# spi-interface-T1M.net
KiCad netlist of a schematic drawn in EAGLE
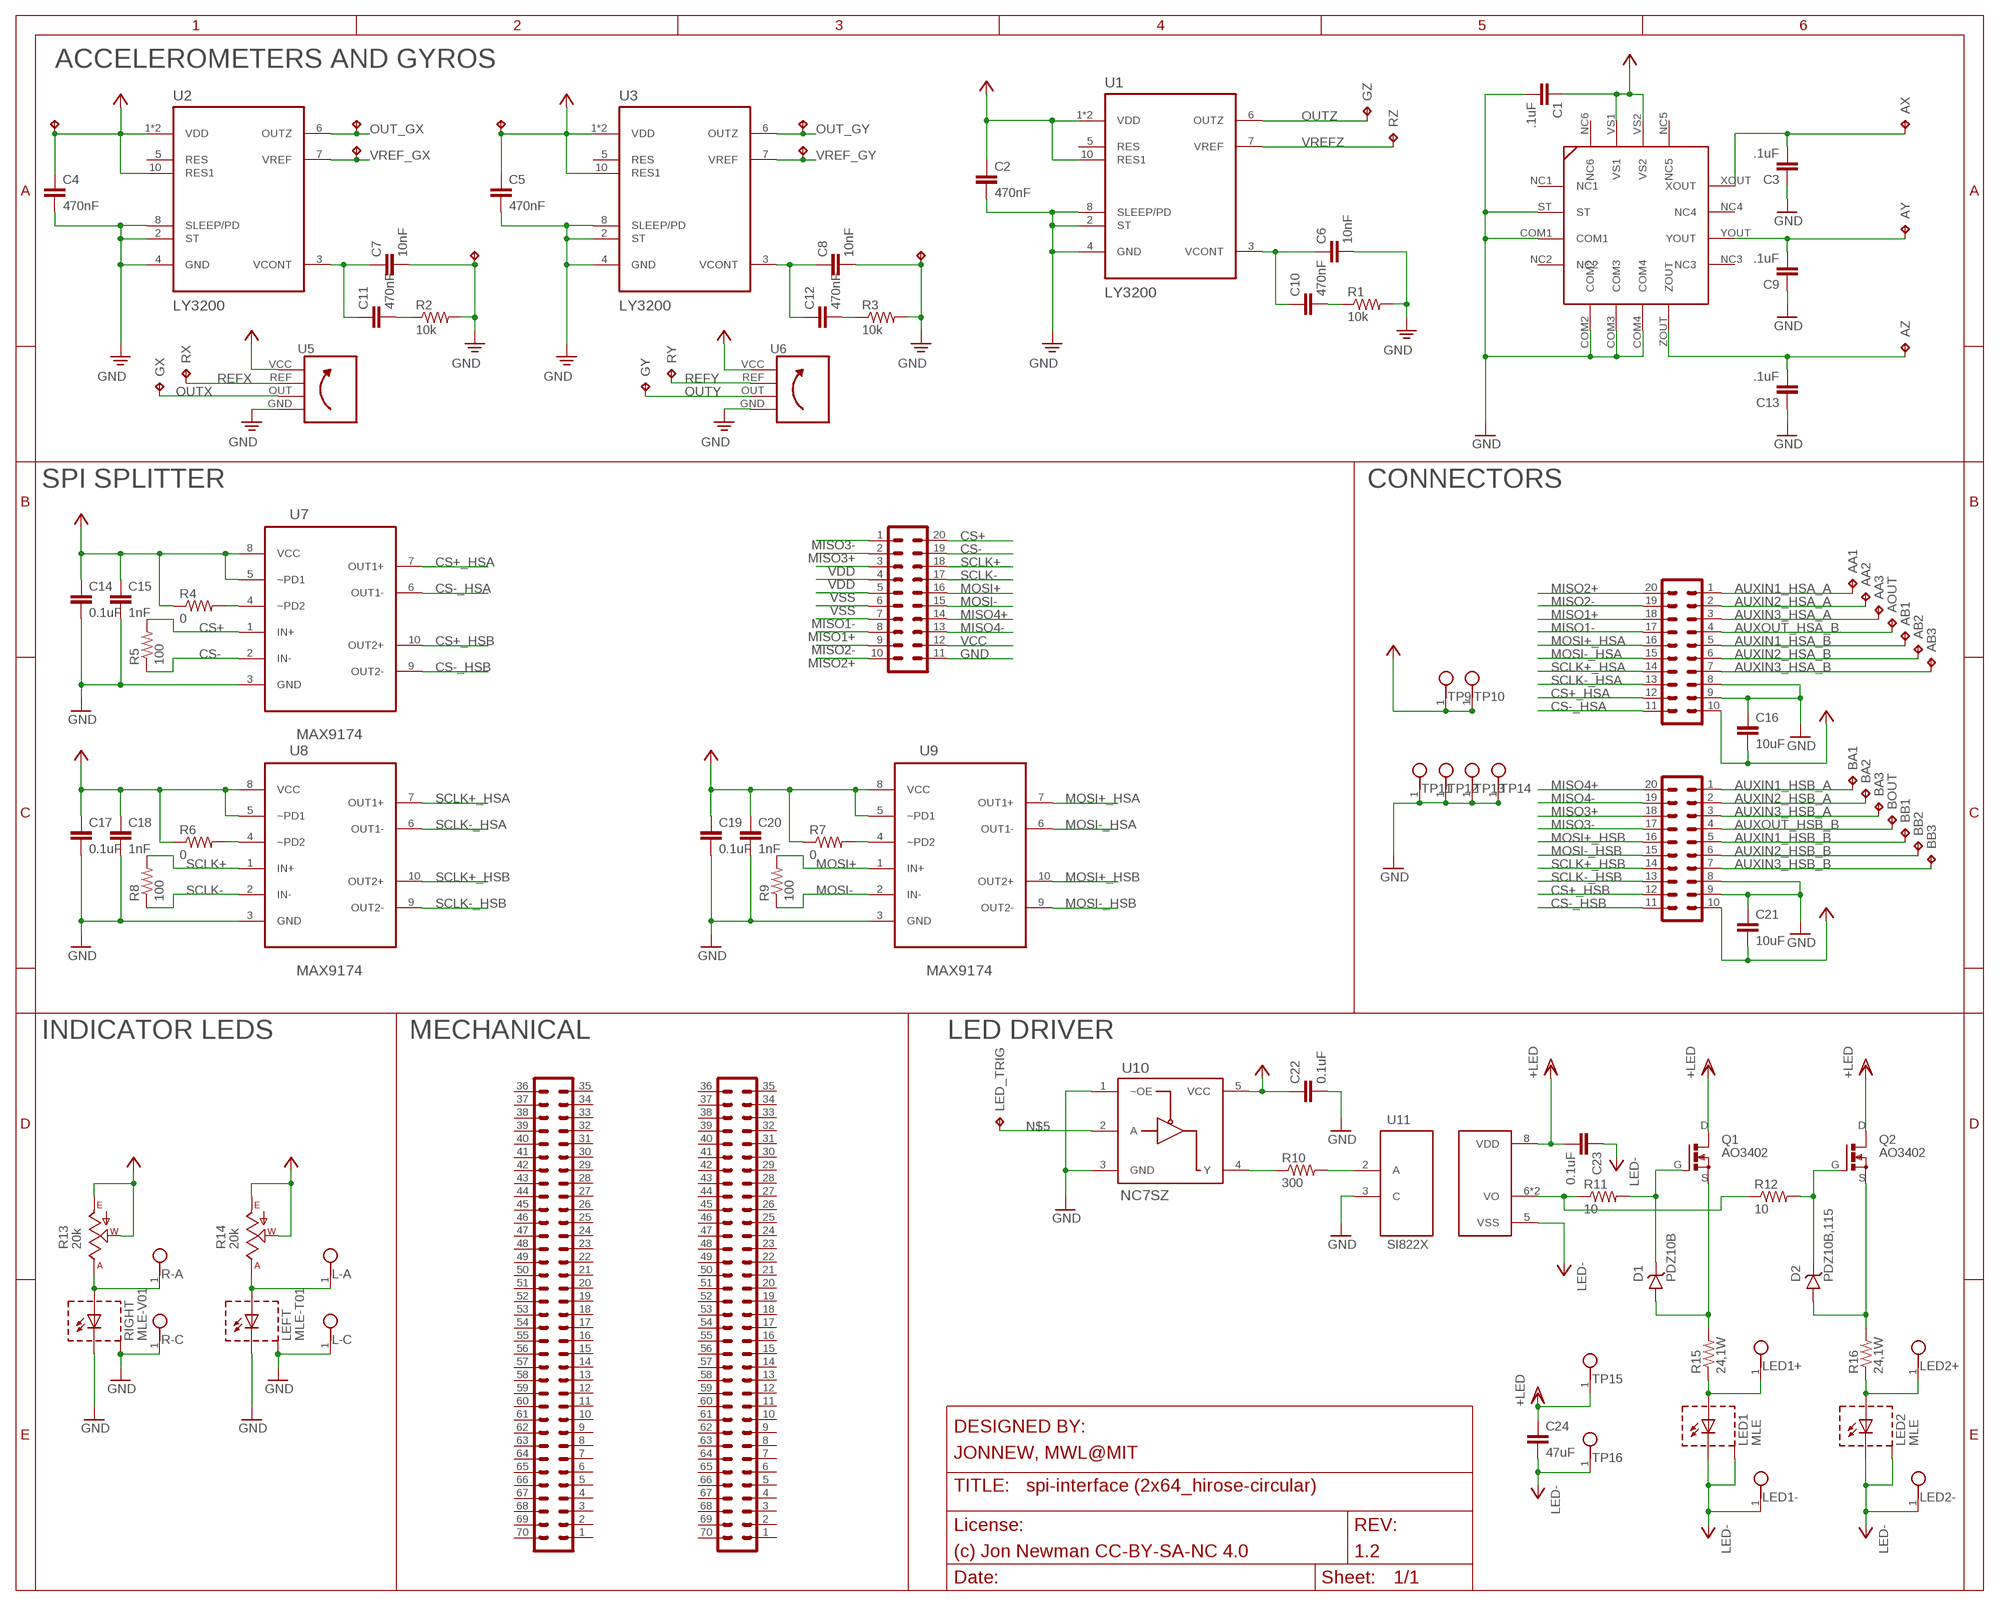
[diagram p0: schematic, sheet 1]

(export (version "E")
  (design (tool "Eeschema 10.0.6"))
  (components
    (comp (ref "AA1")
      (value "TP_0.5MM")
      (footprint "eagle-import:TESTPOINT_0.5MM")
      (libsource (lib "eagle-import") (part "TP_0.5MM"))
    )
    (comp (ref "AA2")
      (value "TP_0.5MM")
      (footprint "eagle-import:TESTPOINT_0.5MM")
      (libsource (lib "eagle-import") (part "TP_0.5MM"))
    )
    (comp (ref "AA3")
      (value "TP_0.5MM")
      (footprint "eagle-import:TESTPOINT_0.5MM")
      (libsource (lib "eagle-import") (part "TP_0.5MM"))
    )
    (comp (ref "AB1")
      (value "TP_0.5MM")
      (footprint "eagle-import:TESTPOINT_0.5MM")
      (libsource (lib "eagle-import") (part "TP_0.5MM"))
    )
    (comp (ref "AB2")
      (value "TP_0.5MM")
      (footprint "eagle-import:TESTPOINT_0.5MM")
      (libsource (lib "eagle-import") (part "TP_0.5MM"))
    )
    (comp (ref "AB3")
      (value "TP_0.5MM")
      (footprint "eagle-import:TESTPOINT_0.5MM")
      (libsource (lib "eagle-import") (part "TP_0.5MM"))
    )
    (comp (ref "AOUT")
      (value "TP_0.5MM")
      (footprint "eagle-import:TESTPOINT_0.5MM")
      (libsource (lib "eagle-import") (part "TP_0.5MM"))
    )
    (comp (ref "AX")
      (value "TP_0.5MM")
      (footprint "eagle-import:TESTPOINT_0.5MM")
      (libsource (lib "eagle-import") (part "TP_0.5MM"))
    )
    (comp (ref "AY")
      (value "TP_0.5MM")
      (footprint "eagle-import:TESTPOINT_0.5MM")
      (libsource (lib "eagle-import") (part "TP_0.5MM"))
    )
    (comp (ref "AZ")
      (value "TP_0.5MM")
      (footprint "eagle-import:TESTPOINT_0.5MM")
      (libsource (lib "eagle-import") (part "TP_0.5MM"))
    )
    (comp (ref "BA1")
      (value "TP_0.5MM")
      (footprint "eagle-import:TESTPOINT_0.5MM")
      (libsource (lib "eagle-import") (part "TP_0.5MM"))
    )
    (comp (ref "BA2")
      (value "TP_0.5MM")
      (footprint "eagle-import:TESTPOINT_0.5MM")
      (libsource (lib "eagle-import") (part "TP_0.5MM"))
    )
    (comp (ref "BA3")
      (value "TP_0.5MM")
      (footprint "eagle-import:TESTPOINT_0.5MM")
      (libsource (lib "eagle-import") (part "TP_0.5MM"))
    )
    (comp (ref "BB1")
      (value "TP_0.5MM")
      (footprint "eagle-import:TESTPOINT_0.5MM")
      (libsource (lib "eagle-import") (part "TP_0.5MM"))
    )
    (comp (ref "BB2")
      (value "TP_0.5MM")
      (footprint "eagle-import:TESTPOINT_0.5MM")
      (libsource (lib "eagle-import") (part "TP_0.5MM"))
    )
    (comp (ref "BB3")
      (value "TP_0.5MM")
      (footprint "eagle-import:TESTPOINT_0.5MM")
      (libsource (lib "eagle-import") (part "TP_0.5MM"))
    )
    (comp (ref "BOUT")
      (value "TP_0.5MM")
      (footprint "eagle-import:TESTPOINT_0.5MM")
      (libsource (lib "eagle-import") (part "TP_0.5MM"))
    )
    (comp (ref "C1")
      (value ".1uF")
      (footprint "eagle-import:0402")
      (libsource (lib "eagle-import") (part "C_0402"))
    )
    (comp (ref "C2")
      (value "470nF")
      (footprint "eagle-import:0201")
      (libsource (lib "eagle-import") (part "jonnew_C_0201"))
    )
    (comp (ref "C3")
      (value ".1uF")
      (footprint "eagle-import:0201")
      (libsource (lib "eagle-import") (part "jonnew_C_0201"))
    )
    (comp (ref "C4")
      (value "470nF")
      (footprint "eagle-import:0201")
      (libsource (lib "eagle-import") (part "jonnew_C_0201"))
    )
    (comp (ref "C5")
      (value "470nF")
      (footprint "eagle-import:0201")
      (libsource (lib "eagle-import") (part "jonnew_C_0201"))
    )
    (comp (ref "C6")
      (value "10nF")
      (footprint "eagle-import:0201")
      (libsource (lib "eagle-import") (part "jonnew_C_0201"))
    )
    (comp (ref "C7")
      (value "10nF")
      (footprint "eagle-import:0201")
      (libsource (lib "eagle-import") (part "jonnew_C_0201"))
    )
    (comp (ref "C8")
      (value "10nF")
      (footprint "eagle-import:0201")
      (libsource (lib "eagle-import") (part "jonnew_C_0201"))
    )
    (comp (ref "C9")
      (value ".1uF")
      (footprint "eagle-import:0201")
      (libsource (lib "eagle-import") (part "jonnew_C_0201"))
    )
    (comp (ref "C10")
      (value "470nF")
      (footprint "eagle-import:0201")
      (libsource (lib "eagle-import") (part "jonnew_C_0201"))
    )
    (comp (ref "C11")
      (value "470nF")
      (footprint "eagle-import:0201")
      (libsource (lib "eagle-import") (part "jonnew_C_0201"))
    )
    (comp (ref "C12")
      (value "470nF")
      (footprint "eagle-import:0201")
      (libsource (lib "eagle-import") (part "jonnew_C_0201"))
    )
    (comp (ref "C13")
      (value ".1uF")
      (footprint "eagle-import:0201")
      (libsource (lib "eagle-import") (part "jonnew_C_0201"))
    )
    (comp (ref "C14")
      (value "0.1uF")
      (footprint "eagle-import:0402")
      (libsource (lib "eagle-import") (part "jonnew_C_0402"))
    )
    (comp (ref "C15")
      (value "1nF")
      (footprint "eagle-import:0201")
      (libsource (lib "eagle-import") (part "jonnew_C_0201"))
    )
    (comp (ref "C16")
      (value "10uF")
      (footprint "eagle-import:0805")
      (fields (field (name "PARTNO") "C2012X5R1Cxxxxxxx"))
      (libsource (lib "eagle-import") (part "C_0805"))
    )
    (comp (ref "C17")
      (value "0.1uF")
      (footprint "eagle-import:0402")
      (libsource (lib "eagle-import") (part "jonnew_C_0402"))
    )
    (comp (ref "C18")
      (value "1nF")
      (footprint "eagle-import:0201")
      (libsource (lib "eagle-import") (part "jonnew_C_0201"))
    )
    (comp (ref "C19")
      (value "0.1uF")
      (footprint "eagle-import:0402")
      (libsource (lib "eagle-import") (part "jonnew_C_0402"))
    )
    (comp (ref "C20")
      (value "1nF")
      (footprint "eagle-import:0201")
      (libsource (lib "eagle-import") (part "jonnew_C_0201"))
    )
    (comp (ref "C21")
      (value "10uF")
      (footprint "eagle-import:0805")
      (fields (field (name "PARTNO") "C2012X5R1Cxxxxxxx"))
      (libsource (lib "eagle-import") (part "C_0805"))
    )
    (comp (ref "C22")
      (value "0.1uF")
      (footprint "eagle-import:0402")
      (libsource (lib "eagle-import") (part "jonnew_C_0402"))
    )
    (comp (ref "C23")
      (value "0.1uF")
      (footprint "eagle-import:0402")
      (libsource (lib "eagle-import") (part "jonnew_C_0402"))
    )
    (comp (ref "C24")
      (value "47uF")
      (footprint "eagle-import:1206")
      (libsource (lib "eagle-import") (part "jonnew_C_1206"))
    )
    (comp (ref "D1")
      (value "PDZ10B")
      (footprint "eagle-import:SOD-323")
      (libsource (lib "eagle-import") (part "Z-DIODE_SOD-323"))
    )
    (comp (ref "D2")
      (value "PDZ10B,115")
      (footprint "eagle-import:SOD-323")
      (libsource (lib "eagle-import") (part "Z-DIODE_SOD-323"))
    )
    (comp (ref "DIO_HSA")
      (value "PINHD-2X10_DF40-20REC")
      (footprint "eagle-import:DF40-20REC")
      (libsource (lib "eagle-import") (part "PINHD-2X10_DF40-20REC"))
    )
    (comp (ref "DIO_HSB")
      (value "PINHD-2X10_DF40-20REC")
      (footprint "eagle-import:DF40-20REC")
      (libsource (lib "eagle-import") (part "PINHD-2X10_DF40-20REC"))
    )
    (comp (ref "GX")
      (value "TP_0.5MM")
      (footprint "eagle-import:TESTPOINT_0.5MM")
      (libsource (lib "eagle-import") (part "TP_0.5MM"))
    )
    (comp (ref "GY")
      (value "TP_0.5MM")
      (footprint "eagle-import:TESTPOINT_0.5MM")
      (libsource (lib "eagle-import") (part "TP_0.5MM"))
    )
    (comp (ref "GZ")
      (value "TP_0.5MM")
      (footprint "eagle-import:TESTPOINT_0.5MM")
      (libsource (lib "eagle-import") (part "TP_0.5MM"))
    )
    (comp (ref "L-A")
      (value "TESTPOINT_SMALL")
      (footprint "eagle-import:TESTPOINT_SMALL")
      (libsource (lib "eagle-import") (part "TESTPOINT_SMALL"))
    )
    (comp (ref "L-C")
      (value "TESTPOINT_SMALL")
      (footprint "eagle-import:TESTPOINT_SMALL")
      (libsource (lib "eagle-import") (part "TESTPOINT_SMALL"))
    )
    (comp (ref "LED1")
      (value "MLE")
      (footprint "eagle-import:LED-MLE")
      (libsource (lib "eagle-import") (part "LED_PKG-BODY"))
    )
    (comp (ref "LED1+")
      (value "TESTPOINT_SMALL")
      (footprint "eagle-import:TESTPOINT_SMALL")
      (libsource (lib "eagle-import") (part "TESTPOINT_SMALL"))
    )
    (comp (ref "LED1-")
      (value "TESTPOINT_SMALL")
      (footprint "eagle-import:TESTPOINT_SMALL")
      (libsource (lib "eagle-import") (part "TESTPOINT_SMALL"))
    )
    (comp (ref "LED2")
      (value "MLE")
      (footprint "eagle-import:LED-MLE")
      (libsource (lib "eagle-import") (part "LED_PKG-BODY"))
    )
    (comp (ref "LED2+")
      (value "TESTPOINT_SMALL")
      (footprint "eagle-import:TESTPOINT_SMALL")
      (libsource (lib "eagle-import") (part "TESTPOINT_SMALL"))
    )
    (comp (ref "LED2-")
      (value "TESTPOINT_SMALL")
      (footprint "eagle-import:TESTPOINT_SMALL")
      (libsource (lib "eagle-import") (part "TESTPOINT_SMALL"))
    )
    (comp (ref "LED_TRIG")
      (value "TP_0.5MM")
      (footprint "eagle-import:TESTPOINT_0.5MM")
      (libsource (lib "eagle-import") (part "TP_0.5MM"))
    )
    (comp (ref "LEFT")
      (value "MLE-T01")
      (footprint "eagle-import:LED-MLE")
      (libsource (lib "eagle-import") (part "LED_PKG-BODY"))
    )
    (comp (ref "MECH_E0B")
      (value "PINHD-2X35_DF40REC")
      (footprint "eagle-import:DF40-70REC")
      (libsource (lib "eagle-import") (part "PINHD-2X35_DF40REC"))
    )
    (comp (ref "MECH_W0B")
      (value "PINHD-2X35_DF40REC")
      (footprint "eagle-import:DF40-70REC")
      (libsource (lib "eagle-import") (part "PINHD-2X35_DF40REC"))
    )
    (comp (ref "Q1")
      (value "AO3402")
      (footprint "eagle-import:SOT23-GSD")
      (libsource (lib "eagle-import") (part "N-MOSFET_SOT23-GSD"))
    )
    (comp (ref "Q2")
      (value "AO3402")
      (footprint "eagle-import:SOT23-GSD")
      (libsource (lib "eagle-import") (part "N-MOSFET_SOT23-GSD"))
    )
    (comp (ref "R-A")
      (value "TESTPOINT_SMALL")
      (footprint "eagle-import:TESTPOINT_SMALL")
      (libsource (lib "eagle-import") (part "TESTPOINT_SMALL"))
    )
    (comp (ref "R-C")
      (value "TESTPOINT_SMALL")
      (footprint "eagle-import:TESTPOINT_SMALL")
      (libsource (lib "eagle-import") (part "TESTPOINT_SMALL"))
    )
    (comp (ref "R1")
      (value "10k")
      (footprint "eagle-import:0201")
      (libsource (lib "eagle-import") (part "R_0201"))
    )
    (comp (ref "R2")
      (value "10k")
      (footprint "eagle-import:0201")
      (libsource (lib "eagle-import") (part "R_0201"))
    )
    (comp (ref "R3")
      (value "10k")
      (footprint "eagle-import:0201")
      (libsource (lib "eagle-import") (part "R_0201"))
    )
    (comp (ref "R4")
      (value "0")
      (footprint "eagle-import:0201")
      (libsource (lib "eagle-import") (part "R_0201"))
    )
    (comp (ref "R5")
      (value "100")
      (footprint "eagle-import:0201")
      (libsource (lib "eagle-import") (part "R_0201"))
    )
    (comp (ref "R6")
      (value "0")
      (footprint "eagle-import:0201")
      (libsource (lib "eagle-import") (part "R_0201"))
    )
    (comp (ref "R7")
      (value "0")
      (footprint "eagle-import:0201")
      (libsource (lib "eagle-import") (part "R_0201"))
    )
    (comp (ref "R8")
      (value "100")
      (footprint "eagle-import:0201")
      (libsource (lib "eagle-import") (part "R_0201"))
    )
    (comp (ref "R9")
      (value "100")
      (footprint "eagle-import:0201")
      (libsource (lib "eagle-import") (part "R_0201"))
    )
    (comp (ref "R10")
      (value "300")
      (footprint "eagle-import:0402")
      (libsource (lib "eagle-import") (part "R_0402"))
    )
    (comp (ref "R11")
      (value "10")
      (footprint "eagle-import:0402")
      (libsource (lib "eagle-import") (part "R_0402"))
    )
    (comp (ref "R12")
      (value "10")
      (footprint "eagle-import:0402")
      (libsource (lib "eagle-import") (part "R_0402"))
    )
    (comp (ref "R13")
      (value "20k")
      (footprint "eagle-import:SM-42_43W")
      (libsource (lib "eagle-import") (part "TRIM_US-SM-42/43W"))
    )
    (comp (ref "R14")
      (value "20k")
      (footprint "eagle-import:SM-42_43W")
      (libsource (lib "eagle-import") (part "TRIM_US-SM-42/43W"))
    )
    (comp (ref "R15")
      (value "24,1W")
      (footprint "eagle-import:0805")
      (libsource (lib "eagle-import") (part "R_0805"))
    )
    (comp (ref "R16")
      (value "24,1W")
      (footprint "eagle-import:0805")
      (libsource (lib "eagle-import") (part "R_0805"))
    )
    (comp (ref "RIGHT")
      (value "MLE-V01")
      (footprint "eagle-import:LED-MLE")
      (libsource (lib "eagle-import") (part "LED_PKG-BODY"))
    )
    (comp (ref "RX")
      (value "TP_0.5MM")
      (footprint "eagle-import:TESTPOINT_0.5MM")
      (libsource (lib "eagle-import") (part "TP_0.5MM"))
    )
    (comp (ref "RY")
      (value "TP_0.5MM")
      (footprint "eagle-import:TESTPOINT_0.5MM")
      (libsource (lib "eagle-import") (part "TP_0.5MM"))
    )
    (comp (ref "RZ")
      (value "TP_0.5MM")
      (footprint "eagle-import:TESTPOINT_0.5MM")
      (libsource (lib "eagle-import") (part "TP_0.5MM"))
    )
    (comp (ref "TETHER")
      (value "T1M-10-T-DV")
      (footprint "eagle-import:T1M-10-T-DV")
      (libsource (lib "eagle-import") (part "PINHD-2X10_T1M"))
    )
    (comp (ref "TP1")
      (value "TPTP08SQ")
      (footprint "eagle-import:TP08SQ")
      (libsource (lib "eagle-import") (part "TPTP08SQ"))
    )
    (comp (ref "TP2")
      (value "TPTP08SQ")
      (footprint "eagle-import:TP08SQ")
      (libsource (lib "eagle-import") (part "TPTP08SQ"))
    )
    (comp (ref "TP3")
      (value "TPTP08SQ")
      (footprint "eagle-import:TP08SQ")
      (libsource (lib "eagle-import") (part "TPTP08SQ"))
    )
    (comp (ref "TP4")
      (value "TPTP08SQ")
      (footprint "eagle-import:TP08SQ")
      (libsource (lib "eagle-import") (part "TPTP08SQ"))
    )
    (comp (ref "TP5")
      (value "TPTP08SQ")
      (footprint "eagle-import:TP08SQ")
      (libsource (lib "eagle-import") (part "TPTP08SQ"))
    )
    (comp (ref "TP6")
      (value "TPTP08SQ")
      (footprint "eagle-import:TP08SQ")
      (libsource (lib "eagle-import") (part "TPTP08SQ"))
    )
    (comp (ref "TP7")
      (value "TPTP08SQ")
      (footprint "eagle-import:TP08SQ")
      (libsource (lib "eagle-import") (part "TPTP08SQ"))
    )
    (comp (ref "TP8")
      (value "TPTP08SQ")
      (footprint "eagle-import:TP08SQ")
      (libsource (lib "eagle-import") (part "TPTP08SQ"))
    )
    (comp (ref "TP9")
      (value "TESTPOINT_SMALL")
      (footprint "eagle-import:TESTPOINT_SMALL")
      (libsource (lib "eagle-import") (part "TESTPOINT_SMALL"))
    )
    (comp (ref "TP10")
      (value "TESTPOINT_SMALL")
      (footprint "eagle-import:TESTPOINT_SMALL")
      (libsource (lib "eagle-import") (part "TESTPOINT_SMALL"))
    )
    (comp (ref "TP11")
      (value "TESTPOINT_SMALL")
      (footprint "eagle-import:TESTPOINT_SMALL")
      (libsource (lib "eagle-import") (part "TESTPOINT_SMALL"))
    )
    (comp (ref "TP12")
      (value "TESTPOINT_SMALL")
      (footprint "eagle-import:TESTPOINT_SMALL")
      (libsource (lib "eagle-import") (part "TESTPOINT_SMALL"))
    )
    (comp (ref "TP13")
      (value "TESTPOINT_SMALL")
      (footprint "eagle-import:TESTPOINT_SMALL")
      (libsource (lib "eagle-import") (part "TESTPOINT_SMALL"))
    )
    (comp (ref "TP14")
      (value "TESTPOINT_SMALL")
      (footprint "eagle-import:TESTPOINT_SMALL")
      (libsource (lib "eagle-import") (part "TESTPOINT_SMALL"))
    )
    (comp (ref "TP15")
      (value "TESTPOINT_SMALL")
      (footprint "eagle-import:TESTPOINT_SMALL")
      (libsource (lib "eagle-import") (part "TESTPOINT_SMALL"))
    )
    (comp (ref "TP16")
      (value "TESTPOINT_SMALL")
      (footprint "eagle-import:TESTPOINT_SMALL")
      (libsource (lib "eagle-import") (part "TESTPOINT_SMALL"))
    )
    (comp (ref "U1")
      (value "LY3200")
      (footprint "eagle-import:LGA-10-COMPACT")
      (libsource (lib "eagle-import") (part "LY3200ALH_LGA-10-COMPACT"))
    )
    (comp (ref "U2")
      (value "LY3200")
      (footprint "eagle-import:LGA-10-COMPACT")
      (libsource (lib "eagle-import") (part "LY3200ALH_LGA-10-COMPACT"))
    )
    (comp (ref "U3")
      (value "LY3200")
      (footprint "eagle-import:LGA-10-COMPACT")
      (libsource (lib "eagle-import") (part "LY3200ALH_LGA-10-COMPACT"))
    )
    (comp (ref "U4")
      (value "ADXL335")
      (footprint "eagle-import:ADXL335")
      (libsource (lib "eagle-import") (part "ADXL335"))
    )
    (comp (ref "U5")
      (value "LY3200-VERT-MODULE")
      (footprint "eagle-import:LY3200-VERT-MODULE")
      (libsource (lib "eagle-import") (part "LY3200-VERT-MODULE"))
    )
    (comp (ref "U6")
      (value "LY3200-VERT-MODULE")
      (footprint "eagle-import:LY3200-VERT-MODULE")
      (libsource (lib "eagle-import") (part "LY3200-VERT-MODULE"))
    )
    (comp (ref "U7")
      (value "MAX9174")
      (footprint "eagle-import:10-UMAX")
      (libsource (lib "eagle-import") (part "MAX9174_UMAX"))
    )
    (comp (ref "U8")
      (value "MAX9174")
      (footprint "eagle-import:10-UMAX")
      (libsource (lib "eagle-import") (part "MAX9174_UMAX"))
    )
    (comp (ref "U9")
      (value "MAX9174")
      (footprint "eagle-import:10-UMAX")
      (libsource (lib "eagle-import") (part "MAX9174_UMAX"))
    )
    (comp (ref "U10")
      (value "NC7SZ")
      (footprint "eagle-import:SOT-23-5")
      (libsource (lib "eagle-import") (part "NC7SZ125"))
    )
    (comp (ref "U11")
      (value "SI822X")
      (footprint "eagle-import:SOIC127P500X400-8N")
      (libsource (lib "eagle-import") (part "SI822X"))
    )
  )
  (nets
    (net (code "1") (name "+LED") (class "Default")
      (node (ref "C23") (pin "2") (pinfunction "2_2") (pintype "passive"))
      (node (ref "C24") (pin "1") (pinfunction "1_1") (pintype "passive"))
      (node (ref "Q1") (pin "D") (pinfunction "D_D") (pintype "bidirectional"))
      (node (ref "Q2") (pin "D") (pinfunction "D_D") (pintype "bidirectional"))
      (node (ref "TETHER") (pin "3") (pinfunction "3_3") (pintype "bidirectional"))
      (node (ref "TETHER") (pin "4") (pinfunction "4_4") (pintype "bidirectional"))
      (node (ref "TP15") (pin "1") (pinfunction "1_1") (pintype "passive"))
      (node (ref "U11") (pin "8") (pinfunction "VDD_8") (pintype "power_in"))
    )
    (net (code "2") (name "/AUXIN1_HSA_A") (class "Default")
      (node (ref "AA1") (pin "1") (pinfunction "TP_1") (pintype "input"))
      (node (ref "DIO_HSA") (pin "1") (pinfunction "1_1") (pintype "bidirectional"))
    )
    (net (code "3") (name "/AUXIN1_HSA_B") (class "Default")
      (node (ref "AB1") (pin "1") (pinfunction "TP_1") (pintype "input"))
      (node (ref "DIO_HSA") (pin "5") (pinfunction "5_5") (pintype "bidirectional"))
    )
    (net (code "4") (name "/AUXIN1_HSB_A") (class "Default")
      (node (ref "BA1") (pin "1") (pinfunction "TP_1") (pintype "input"))
      (node (ref "DIO_HSB") (pin "1") (pinfunction "1_1") (pintype "bidirectional"))
    )
    (net (code "5") (name "/AUXIN1_HSB_B") (class "Default")
      (node (ref "BB1") (pin "1") (pinfunction "TP_1") (pintype "input"))
      (node (ref "DIO_HSB") (pin "5") (pinfunction "5_5") (pintype "bidirectional"))
    )
    (net (code "6") (name "/AUXIN2_HSA_A") (class "Default")
      (node (ref "AA2") (pin "1") (pinfunction "TP_1") (pintype "input"))
      (node (ref "DIO_HSA") (pin "2") (pinfunction "2_2") (pintype "bidirectional"))
    )
    (net (code "7") (name "/AUXIN2_HSA_B") (class "Default")
      (node (ref "AB2") (pin "1") (pinfunction "TP_1") (pintype "input"))
      (node (ref "DIO_HSA") (pin "6") (pinfunction "6_6") (pintype "bidirectional"))
    )
    (net (code "8") (name "/AUXIN2_HSB_A") (class "Default")
      (node (ref "BA2") (pin "1") (pinfunction "TP_1") (pintype "input"))
      (node (ref "DIO_HSB") (pin "2") (pinfunction "2_2") (pintype "bidirectional"))
    )
    (net (code "9") (name "/AUXIN2_HSB_B") (class "Default")
      (node (ref "BB2") (pin "1") (pinfunction "TP_1") (pintype "input"))
      (node (ref "DIO_HSB") (pin "6") (pinfunction "6_6") (pintype "bidirectional"))
    )
    (net (code "10") (name "/AUXIN3_HSA_A") (class "Default")
      (node (ref "AA3") (pin "1") (pinfunction "TP_1") (pintype "input"))
      (node (ref "DIO_HSA") (pin "3") (pinfunction "3_3") (pintype "bidirectional"))
    )
    (net (code "11") (name "/AUXIN3_HSA_B") (class "Default")
      (node (ref "AB3") (pin "1") (pinfunction "TP_1") (pintype "input"))
      (node (ref "DIO_HSA") (pin "7") (pinfunction "7_7") (pintype "bidirectional"))
    )
    (net (code "12") (name "/AUXIN3_HSB_A") (class "Default")
      (node (ref "BA3") (pin "1") (pinfunction "TP_1") (pintype "input"))
      (node (ref "DIO_HSB") (pin "3") (pinfunction "3_3") (pintype "bidirectional"))
    )
    (net (code "13") (name "/AUXIN3_HSB_B") (class "Default")
      (node (ref "BB3") (pin "1") (pinfunction "TP_1") (pintype "input"))
      (node (ref "DIO_HSB") (pin "7") (pinfunction "7_7") (pintype "bidirectional"))
    )
    (net (code "14") (name "/AUXOUT_HSA_B") (class "Default")
      (node (ref "AOUT") (pin "1") (pinfunction "TP_1") (pintype "input"))
      (node (ref "DIO_HSA") (pin "4") (pinfunction "4_4") (pintype "bidirectional"))
    )
    (net (code "15") (name "/AUXOUT_HSB_B") (class "Default")
      (node (ref "BOUT") (pin "1") (pinfunction "TP_1") (pintype "input"))
      (node (ref "DIO_HSB") (pin "4") (pinfunction "4_4") (pintype "bidirectional"))
    )
    (net (code "16") (name "/CS+") (class "Default")
      (node (ref "R5") (pin "2") (pinfunction "2_2") (pintype "passive"))
      (node (ref "TETHER") (pin "20") (pinfunction "20_20") (pintype "bidirectional"))
      (node (ref "U7") (pin "1") (pinfunction "IN+_1") (pintype "input"))
    )
    (net (code "17") (name "/CS+_HSA") (class "Default")
      (node (ref "DIO_HSA") (pin "12") (pinfunction "12_12") (pintype "bidirectional"))
      (node (ref "U7") (pin "7") (pinfunction "OUT1+_7") (pintype "output"))
    )
    (net (code "18") (name "/CS+_HSB") (class "Default")
      (node (ref "DIO_HSB") (pin "12") (pinfunction "12_12") (pintype "bidirectional"))
      (node (ref "U7") (pin "10") (pinfunction "OUT2+_10") (pintype "output"))
    )
    (net (code "19") (name "/CS-") (class "Default")
      (node (ref "R5") (pin "1") (pinfunction "1_1") (pintype "passive"))
      (node (ref "TETHER") (pin "19") (pinfunction "19_19") (pintype "bidirectional"))
      (node (ref "U7") (pin "2") (pinfunction "IN-_2") (pintype "input"))
    )
    (net (code "20") (name "/CS-_HSA") (class "Default")
      (node (ref "DIO_HSA") (pin "11") (pinfunction "11_11") (pintype "bidirectional"))
      (node (ref "U7") (pin "6") (pinfunction "OUT1-_6") (pintype "output"))
    )
    (net (code "21") (name "/CS-_HSB") (class "Default")
      (node (ref "DIO_HSB") (pin "11") (pinfunction "11_11") (pintype "bidirectional"))
      (node (ref "U7") (pin "9") (pinfunction "OUT2-_9") (pintype "output"))
    )
    (net (code "22") (name "/MISO1+") (class "Default")
      (node (ref "DIO_HSA") (pin "18") (pinfunction "18_18") (pintype "bidirectional"))
      (node (ref "TETHER") (pin "8") (pinfunction "8_8") (pintype "bidirectional"))
    )
    (net (code "23") (name "/MISO1-") (class "Default")
      (node (ref "DIO_HSA") (pin "17") (pinfunction "17_17") (pintype "bidirectional"))
      (node (ref "TETHER") (pin "7") (pinfunction "7_7") (pintype "bidirectional"))
    )
    (net (code "24") (name "/MISO2+") (class "Default")
      (node (ref "DIO_HSA") (pin "20") (pinfunction "20_20") (pintype "bidirectional"))
      (node (ref "TETHER") (pin "10") (pinfunction "10_10") (pintype "bidirectional"))
    )
    (net (code "25") (name "/MISO2-") (class "Default")
      (node (ref "DIO_HSA") (pin "19") (pinfunction "19_19") (pintype "bidirectional"))
      (node (ref "TETHER") (pin "9") (pinfunction "9_9") (pintype "bidirectional"))
    )
    (net (code "26") (name "/MISO3+") (class "Default")
      (node (ref "DIO_HSB") (pin "18") (pinfunction "18_18") (pintype "bidirectional"))
      (node (ref "TETHER") (pin "2") (pinfunction "2_2") (pintype "bidirectional"))
    )
    (net (code "27") (name "/MISO3-") (class "Default")
      (node (ref "DIO_HSB") (pin "17") (pinfunction "17_17") (pintype "bidirectional"))
      (node (ref "TETHER") (pin "1") (pinfunction "1_1") (pintype "bidirectional"))
    )
    (net (code "28") (name "/MISO4+") (class "Default")
      (node (ref "DIO_HSB") (pin "20") (pinfunction "20_20") (pintype "bidirectional"))
      (node (ref "TETHER") (pin "14") (pinfunction "14_14") (pintype "bidirectional"))
    )
    (net (code "29") (name "/MISO4-") (class "Default")
      (node (ref "DIO_HSB") (pin "19") (pinfunction "19_19") (pintype "bidirectional"))
      (node (ref "TETHER") (pin "13") (pinfunction "13_13") (pintype "bidirectional"))
    )
    (net (code "30") (name "/MOSI+") (class "Default")
      (node (ref "R9") (pin "2") (pinfunction "2_2") (pintype "passive"))
      (node (ref "TETHER") (pin "16") (pinfunction "16_16") (pintype "bidirectional"))
      (node (ref "U9") (pin "1") (pinfunction "IN+_1") (pintype "input"))
    )
    (net (code "31") (name "/MOSI+_HSA") (class "Default")
      (node (ref "DIO_HSA") (pin "16") (pinfunction "16_16") (pintype "bidirectional"))
      (node (ref "U9") (pin "7") (pinfunction "OUT1+_7") (pintype "output"))
    )
    (net (code "32") (name "/MOSI+_HSB") (class "Default")
      (node (ref "DIO_HSB") (pin "16") (pinfunction "16_16") (pintype "bidirectional"))
      (node (ref "U9") (pin "10") (pinfunction "OUT2+_10") (pintype "output"))
    )
    (net (code "33") (name "/MOSI-") (class "Default")
      (node (ref "R9") (pin "1") (pinfunction "1_1") (pintype "passive"))
      (node (ref "TETHER") (pin "15") (pinfunction "15_15") (pintype "bidirectional"))
      (node (ref "U9") (pin "2") (pinfunction "IN-_2") (pintype "input"))
    )
    (net (code "34") (name "/MOSI-_HSA") (class "Default")
      (node (ref "DIO_HSA") (pin "15") (pinfunction "15_15") (pintype "bidirectional"))
      (node (ref "U9") (pin "6") (pinfunction "OUT1-_6") (pintype "output"))
    )
    (net (code "35") (name "/MOSI-_HSB") (class "Default")
      (node (ref "DIO_HSB") (pin "15") (pinfunction "15_15") (pintype "bidirectional"))
      (node (ref "U9") (pin "9") (pinfunction "OUT2-_9") (pintype "output"))
    )
    (net (code "36") (name "/N$5") (class "Default")
      (node (ref "LED_TRIG") (pin "1") (pinfunction "TP_1") (pintype "input"))
      (node (ref "U10") (pin "2") (pinfunction "A_2") (pintype "input"))
    )
    (net (code "37") (name "/OUTX") (class "Default")
      (node (ref "GX") (pin "1") (pinfunction "TP_1") (pintype "input"))
      (node (ref "U5") (pin "OUT") (pinfunction "OUT_OUT") (pintype "output"))
    )
    (net (code "38") (name "/OUTY") (class "Default")
      (node (ref "GY") (pin "1") (pinfunction "TP_1") (pintype "input"))
      (node (ref "U6") (pin "OUT") (pinfunction "OUT_OUT") (pintype "output"))
    )
    (net (code "39") (name "/OUTZ") (class "Default")
      (node (ref "GZ") (pin "1") (pinfunction "TP_1") (pintype "input"))
      (node (ref "U1") (pin "6") (pinfunction "OUTZ_6") (pintype "output"))
    )
    (net (code "40") (name "/OUT_GX") (class "Default")
      (node (ref "TP2") (pin "TP") (pinfunction "TP_TP") (pintype "input"))
      (node (ref "U2") (pin "6") (pinfunction "OUTZ_6") (pintype "output"))
    )
    (net (code "41") (name "/OUT_GY") (class "Default")
      (node (ref "TP4") (pin "TP") (pinfunction "TP_TP") (pintype "input"))
      (node (ref "U3") (pin "6") (pinfunction "OUTZ_6") (pintype "output"))
    )
    (net (code "42") (name "/REFX") (class "Default")
      (node (ref "RX") (pin "1") (pinfunction "TP_1") (pintype "input"))
      (node (ref "U5") (pin "REF") (pinfunction "REF_REF") (pintype "output"))
    )
    (net (code "43") (name "/REFY") (class "Default")
      (node (ref "RY") (pin "1") (pinfunction "TP_1") (pintype "input"))
      (node (ref "U6") (pin "REF") (pinfunction "REF_REF") (pintype "output"))
    )
    (net (code "44") (name "/SCLK+") (class "Default")
      (node (ref "R8") (pin "2") (pinfunction "2_2") (pintype "passive"))
      (node (ref "TETHER") (pin "18") (pinfunction "18_18") (pintype "bidirectional"))
      (node (ref "U8") (pin "1") (pinfunction "IN+_1") (pintype "input"))
    )
    (net (code "45") (name "/SCLK+_HSA") (class "Default")
      (node (ref "DIO_HSA") (pin "14") (pinfunction "14_14") (pintype "bidirectional"))
      (node (ref "U8") (pin "7") (pinfunction "OUT1+_7") (pintype "output"))
    )
    (net (code "46") (name "/SCLK+_HSB") (class "Default")
      (node (ref "DIO_HSB") (pin "14") (pinfunction "14_14") (pintype "bidirectional"))
      (node (ref "U8") (pin "10") (pinfunction "OUT2+_10") (pintype "output"))
    )
    (net (code "47") (name "/SCLK-") (class "Default")
      (node (ref "R8") (pin "1") (pinfunction "1_1") (pintype "passive"))
      (node (ref "TETHER") (pin "17") (pinfunction "17_17") (pintype "bidirectional"))
      (node (ref "U8") (pin "2") (pinfunction "IN-_2") (pintype "input"))
    )
    (net (code "48") (name "/SCLK-_HSA") (class "Default")
      (node (ref "DIO_HSA") (pin "13") (pinfunction "13_13") (pintype "bidirectional"))
      (node (ref "U8") (pin "6") (pinfunction "OUT1-_6") (pintype "output"))
    )
    (net (code "49") (name "/SCLK-_HSB") (class "Default")
      (node (ref "DIO_HSB") (pin "13") (pinfunction "13_13") (pintype "bidirectional"))
      (node (ref "U8") (pin "9") (pinfunction "OUT2-_9") (pintype "output"))
    )
    (net (code "50") (name "/VREFZ") (class "Default")
      (node (ref "RZ") (pin "1") (pinfunction "TP_1") (pintype "input"))
      (node (ref "U1") (pin "7") (pinfunction "VREF_7") (pintype "output"))
    )
    (net (code "51") (name "/VREF_GX") (class "Default")
      (node (ref "TP5") (pin "TP") (pinfunction "TP_TP") (pintype "input"))
      (node (ref "U2") (pin "7") (pinfunction "VREF_7") (pintype "output"))
    )
    (net (code "52") (name "/VREF_GY") (class "Default")
      (node (ref "TP6") (pin "TP") (pinfunction "TP_TP") (pintype "input"))
      (node (ref "U3") (pin "7") (pinfunction "VREF_7") (pintype "output"))
    )
    (net (code "53") (name "GND") (class "Default")
      (node (ref "C1") (pin "2") (pinfunction "2_2") (pintype "passive"))
      (node (ref "C13") (pin "1") (pinfunction "1_1") (pintype "passive"))
      (node (ref "C14") (pin "2") (pinfunction "2_2") (pintype "passive"))
      (node (ref "C15") (pin "2") (pinfunction "2_2") (pintype "passive"))
      (node (ref "C16") (pin "1") (pinfunction "1_1") (pintype "passive"))
      (node (ref "C17") (pin "2") (pinfunction "2_2") (pintype "passive"))
      (node (ref "C18") (pin "2") (pinfunction "2_2") (pintype "passive"))
      (node (ref "C19") (pin "2") (pinfunction "2_2") (pintype "passive"))
      (node (ref "C2") (pin "2") (pinfunction "2_2") (pintype "passive"))
      (node (ref "C20") (pin "2") (pinfunction "2_2") (pintype "passive"))
      (node (ref "C21") (pin "1") (pinfunction "1_1") (pintype "passive"))
      (node (ref "C22") (pin "2") (pinfunction "2_2") (pintype "passive"))
      (node (ref "C3") (pin "1") (pinfunction "1_1") (pintype "passive"))
      (node (ref "C4") (pin "2") (pinfunction "2_2") (pintype "passive"))
      (node (ref "C5") (pin "2") (pinfunction "2_2") (pintype "passive"))
      (node (ref "C6") (pin "2") (pinfunction "2_2") (pintype "passive"))
      (node (ref "C7") (pin "2") (pinfunction "2_2") (pintype "passive"))
      (node (ref "C8") (pin "2") (pinfunction "2_2") (pintype "passive"))
      (node (ref "C9") (pin "1") (pinfunction "1_1") (pintype "passive"))
      (node (ref "DIO_HSA") (pin "8") (pinfunction "8_8") (pintype "bidirectional"))
      (node (ref "DIO_HSA") (pin "9") (pinfunction "9_9") (pintype "bidirectional"))
      (node (ref "DIO_HSB") (pin "8") (pinfunction "8_8") (pintype "bidirectional"))
      (node (ref "DIO_HSB") (pin "9") (pinfunction "9_9") (pintype "bidirectional"))
      (node (ref "L-C") (pin "1") (pinfunction "1_1") (pintype "passive"))
      (node (ref "LEFT") (pin "C1") (pinfunction "C_C1") (pintype "passive"))
      (node (ref "LEFT") (pin "C2") (pinfunction "C_C2") (pintype "passive"))
      (node (ref "LEFT") (pin "HS") (pinfunction "BODY_HS") (pintype "passive"))
      (node (ref "R-C") (pin "1") (pinfunction "1_1") (pintype "passive"))
      (node (ref "R1") (pin "2") (pinfunction "2_2") (pintype "passive"))
      (node (ref "R2") (pin "2") (pinfunction "2_2") (pintype "passive"))
      (node (ref "R3") (pin "2") (pinfunction "2_2") (pintype "passive"))
      (node (ref "RIGHT") (pin "C1") (pinfunction "C_C1") (pintype "passive"))
      (node (ref "RIGHT") (pin "C2") (pinfunction "C_C2") (pintype "passive"))
      (node (ref "RIGHT") (pin "HS") (pinfunction "BODY_HS") (pintype "passive"))
      (node (ref "TETHER") (pin "11") (pinfunction "11_11") (pintype "bidirectional"))
      (node (ref "TP11") (pin "1") (pinfunction "1_1") (pintype "passive"))
      (node (ref "TP12") (pin "1") (pinfunction "1_1") (pintype "passive"))
      (node (ref "TP13") (pin "1") (pinfunction "1_1") (pintype "passive"))
      (node (ref "TP14") (pin "1") (pinfunction "1_1") (pintype "passive"))
      (node (ref "TP7") (pin "TP") (pinfunction "TP_TP") (pintype "input"))
      (node (ref "TP8") (pin "TP") (pinfunction "TP_TP") (pintype "input"))
      (node (ref "U1") (pin "2") (pinfunction "ST_2") (pintype "bidirectional"))
      (node (ref "U1") (pin "4") (pinfunction "GND_4") (pintype "power_in"))
      (node (ref "U1") (pin "8") (pinfunction "SLEEP/PD_8") (pintype "bidirectional"))
      (node (ref "U10") (pin "1") (pinfunction "~{OE}_1") (pintype "input"))
      (node (ref "U10") (pin "3") (pinfunction "GND_3") (pintype "power_in"))
      (node (ref "U11") (pin "3") (pinfunction "C_3") (pintype "bidirectional"))
      (node (ref "U2") (pin "2") (pinfunction "ST_2") (pintype "bidirectional"))
      (node (ref "U2") (pin "4") (pinfunction "GND_4") (pintype "power_in"))
      (node (ref "U2") (pin "8") (pinfunction "SLEEP/PD_8") (pintype "bidirectional"))
      (node (ref "U3") (pin "2") (pinfunction "ST_2") (pintype "bidirectional"))
      (node (ref "U3") (pin "4") (pinfunction "GND_4") (pintype "power_in"))
      (node (ref "U3") (pin "8") (pinfunction "SLEEP/PD_8") (pintype "bidirectional"))
      (node (ref "U4") (pin "COM1") (pinfunction "COM1_COM1") (pintype "bidirectional"))
      (node (ref "U4") (pin "COM2") (pinfunction "COM2_COM2") (pintype "bidirectional"))
      (node (ref "U4") (pin "COM3") (pinfunction "COM3_COM3") (pintype "bidirectional"))
      (node (ref "U4") (pin "COM4") (pinfunction "COM4_COM4") (pintype "bidirectional"))
      (node (ref "U4") (pin "ST") (pinfunction "ST_ST") (pintype "bidirectional"))
      (node (ref "U5") (pin "GND") (pinfunction "GND_GND") (pintype "power_in"))
      (node (ref "U6") (pin "GND") (pinfunction "GND_GND") (pintype "power_in"))
      (node (ref "U7") (pin "3") (pinfunction "GND_3") (pintype "power_in"))
      (node (ref "U8") (pin "3") (pinfunction "GND_3") (pintype "power_in"))
      (node (ref "U9") (pin "3") (pinfunction "GND_3") (pintype "power_in"))
    )
    (net (code "54") (name "LED-") (class "Default")
      (node (ref "C23") (pin "1") (pinfunction "1_1") (pintype "passive"))
      (node (ref "C24") (pin "2") (pinfunction "2_2") (pintype "passive"))
      (node (ref "LED1") (pin "C1") (pinfunction "C_C1") (pintype "passive"))
      (node (ref "LED1") (pin "C2") (pinfunction "C_C2") (pintype "passive"))
      (node (ref "LED1") (pin "HS") (pinfunction "BODY_HS") (pintype "passive"))
      (node (ref "LED1-") (pin "1") (pinfunction "1_1") (pintype "passive"))
      (node (ref "LED2") (pin "C1") (pinfunction "C_C1") (pintype "passive"))
      (node (ref "LED2") (pin "C2") (pinfunction "C_C2") (pintype "passive"))
      (node (ref "LED2") (pin "HS") (pinfunction "BODY_HS") (pintype "passive"))
      (node (ref "LED2-") (pin "1") (pinfunction "1_1") (pintype "passive"))
      (node (ref "TETHER") (pin "5") (pinfunction "5_5") (pintype "bidirectional"))
      (node (ref "TETHER") (pin "6") (pinfunction "6_6") (pintype "bidirectional"))
      (node (ref "TP16") (pin "1") (pinfunction "1_1") (pintype "passive"))
      (node (ref "U11") (pin "5") (pinfunction "VSS_5") (pintype "power_in"))
    )
    (net (code "55") (name "Net-(AX-TP)") (class "Default")
      (node (ref "AX") (pin "1") (pinfunction "TP_1") (pintype "input"))
      (node (ref "C3") (pin "2") (pinfunction "2_2") (pintype "passive"))
      (node (ref "U4") (pin "XOUT") (pinfunction "XOUT_XOUT") (pintype "bidirectional"))
    )
    (net (code "56") (name "Net-(AY-TP)") (class "Default")
      (node (ref "AY") (pin "1") (pinfunction "TP_1") (pintype "input"))
      (node (ref "C9") (pin "2") (pinfunction "2_2") (pintype "passive"))
      (node (ref "U4") (pin "YOUT") (pinfunction "YOUT_YOUT") (pintype "bidirectional"))
    )
    (net (code "57") (name "Net-(AZ-TP)") (class "Default")
      (node (ref "AZ") (pin "1") (pinfunction "TP_1") (pintype "input"))
      (node (ref "C13") (pin "2") (pinfunction "2_2") (pintype "passive"))
      (node (ref "U4") (pin "ZOUT") (pinfunction "ZOUT_ZOUT") (pintype "bidirectional"))
    )
    (net (code "58") (name "Net-(C10-Pad2)") (class "Default")
      (node (ref "C10") (pin "2") (pinfunction "2_2") (pintype "passive"))
      (node (ref "R1") (pin "1") (pinfunction "1_1") (pintype "passive"))
    )
    (net (code "59") (name "Net-(C11-Pad2)") (class "Default")
      (node (ref "C11") (pin "2") (pinfunction "2_2") (pintype "passive"))
      (node (ref "R2") (pin "1") (pinfunction "1_1") (pintype "passive"))
    )
    (net (code "60") (name "Net-(C12-Pad2)") (class "Default")
      (node (ref "C12") (pin "2") (pinfunction "2_2") (pintype "passive"))
      (node (ref "R3") (pin "1") (pinfunction "1_1") (pintype "passive"))
    )
    (net (code "61") (name "Net-(D1-PadA)") (class "Default")
      (node (ref "D1") (pin "A") (pinfunction "A_A") (pintype "passive"))
      (node (ref "Q1") (pin "S") (pinfunction "S_S") (pintype "bidirectional"))
      (node (ref "R15") (pin "2") (pinfunction "2_2") (pintype "passive"))
    )
    (net (code "62") (name "Net-(D1-PadC)") (class "Default")
      (node (ref "D1") (pin "C") (pinfunction "C_C") (pintype "passive"))
      (node (ref "Q1") (pin "G") (pinfunction "G_G") (pintype "bidirectional"))
      (node (ref "R11") (pin "2") (pinfunction "2_2") (pintype "passive"))
    )
    (net (code "63") (name "Net-(D2-PadA)") (class "Default")
      (node (ref "D2") (pin "A") (pinfunction "A_A") (pintype "passive"))
      (node (ref "Q2") (pin "S") (pinfunction "S_S") (pintype "bidirectional"))
      (node (ref "R16") (pin "2") (pinfunction "2_2") (pintype "passive"))
    )
    (net (code "64") (name "Net-(D2-PadC)") (class "Default")
      (node (ref "D2") (pin "C") (pinfunction "C_C") (pintype "passive"))
      (node (ref "Q2") (pin "G") (pinfunction "G_G") (pintype "bidirectional"))
      (node (ref "R12") (pin "2") (pinfunction "2_2") (pintype "passive"))
    )
    (net (code "65") (name "Net-(LED1+-Pad1)") (class "Default")
      (node (ref "LED1") (pin "A1") (pinfunction "A_A1") (pintype "passive"))
      (node (ref "LED1") (pin "A2") (pinfunction "A_A2") (pintype "passive"))
      (node (ref "LED1+") (pin "1") (pinfunction "1_1") (pintype "passive"))
      (node (ref "R15") (pin "1") (pinfunction "1_1") (pintype "passive"))
    )
    (net (code "66") (name "Net-(LED2+-Pad1)") (class "Default")
      (node (ref "LED2") (pin "A1") (pinfunction "A_A1") (pintype "passive"))
      (node (ref "LED2") (pin "A2") (pinfunction "A_A2") (pintype "passive"))
      (node (ref "LED2+") (pin "1") (pinfunction "1_1") (pintype "passive"))
      (node (ref "R16") (pin "1") (pinfunction "1_1") (pintype "passive"))
    )
    (net (code "67") (name "Net-(R11-Pad1)") (class "Default")
      (node (ref "R11") (pin "1") (pinfunction "1_1") (pintype "passive"))
      (node (ref "R12") (pin "1") (pinfunction "1_1") (pintype "passive"))
      (node (ref "U11") (pin "6") (pinfunction "VO_6") (pintype "bidirectional"))
      (node (ref "U11") (pin "7") (pinfunction "VO_7") (pintype "bidirectional"))
    )
    (net (code "68") (name "Net-(R13-A)") (class "Default")
      (node (ref "R-A") (pin "1") (pinfunction "1_1") (pintype "passive"))
      (node (ref "R13") (pin "1") (pinfunction "A_1") (pintype "passive"))
      (node (ref "RIGHT") (pin "A1") (pinfunction "A_A1") (pintype "passive"))
      (node (ref "RIGHT") (pin "A2") (pinfunction "A_A2") (pintype "passive"))
    )
    (net (code "69") (name "Net-(R14-A)") (class "Default")
      (node (ref "L-A") (pin "1") (pinfunction "1_1") (pintype "passive"))
      (node (ref "LEFT") (pin "A1") (pinfunction "A_A1") (pintype "passive"))
      (node (ref "LEFT") (pin "A2") (pinfunction "A_A2") (pintype "passive"))
      (node (ref "R14") (pin "1") (pinfunction "A_1") (pintype "passive"))
    )
    (net (code "70") (name "Net-(U1-VCONT)") (class "Default")
      (node (ref "C10") (pin "1") (pinfunction "1_1") (pintype "passive"))
      (node (ref "C6") (pin "1") (pinfunction "1_1") (pintype "passive"))
      (node (ref "U1") (pin "3") (pinfunction "VCONT_3") (pintype "passive"))
    )
    (net (code "71") (name "Net-(U2-VCONT)") (class "Default")
      (node (ref "C11") (pin "1") (pinfunction "1_1") (pintype "passive"))
      (node (ref "C7") (pin "1") (pinfunction "1_1") (pintype "passive"))
      (node (ref "U2") (pin "3") (pinfunction "VCONT_3") (pintype "passive"))
    )
    (net (code "72") (name "Net-(U3-VCONT)") (class "Default")
      (node (ref "C12") (pin "1") (pinfunction "1_1") (pintype "passive"))
      (node (ref "C8") (pin "1") (pinfunction "1_1") (pintype "passive"))
      (node (ref "U3") (pin "3") (pinfunction "VCONT_3") (pintype "passive"))
    )
    (net (code "73") (name "Net-(U7-~{PD2})") (class "Default")
      (node (ref "R4") (pin "2") (pinfunction "2_2") (pintype "passive"))
      (node (ref "U7") (pin "4") (pinfunction "~{PD2}_4") (pintype "passive"))
    )
    (net (code "74") (name "Net-(U8-~{PD2})") (class "Default")
      (node (ref "R6") (pin "2") (pinfunction "2_2") (pintype "passive"))
      (node (ref "U8") (pin "4") (pinfunction "~{PD2}_4") (pintype "passive"))
    )
    (net (code "75") (name "Net-(U9-~{PD2})") (class "Default")
      (node (ref "R7") (pin "2") (pinfunction "2_2") (pintype "passive"))
      (node (ref "U9") (pin "4") (pinfunction "~{PD2}_4") (pintype "passive"))
    )
    (net (code "76") (name "Net-(U10-Y)") (class "Default")
      (node (ref "R10") (pin "1") (pinfunction "1_1") (pintype "passive"))
      (node (ref "U10") (pin "4") (pinfunction "Y_4") (pintype "output"))
    )
    (net (code "77") (name "Net-(U11-A)") (class "Default")
      (node (ref "R10") (pin "2") (pinfunction "2_2") (pintype "passive"))
      (node (ref "U11") (pin "2") (pinfunction "A_2") (pintype "bidirectional"))
    )
    (net (code "78") (name "VCC") (class "Default")
      (node (ref "C1") (pin "1") (pinfunction "1_1") (pintype "passive"))
      (node (ref "C14") (pin "1") (pinfunction "1_1") (pintype "passive"))
      (node (ref "C15") (pin "1") (pinfunction "1_1") (pintype "passive"))
      (node (ref "C16") (pin "2") (pinfunction "2_2") (pintype "passive"))
      (node (ref "C17") (pin "1") (pinfunction "1_1") (pintype "passive"))
      (node (ref "C18") (pin "1") (pinfunction "1_1") (pintype "passive"))
      (node (ref "C19") (pin "1") (pinfunction "1_1") (pintype "passive"))
      (node (ref "C2") (pin "1") (pinfunction "1_1") (pintype "passive"))
      (node (ref "C20") (pin "1") (pinfunction "1_1") (pintype "passive"))
      (node (ref "C21") (pin "2") (pinfunction "2_2") (pintype "passive"))
      (node (ref "C22") (pin "1") (pinfunction "1_1") (pintype "passive"))
      (node (ref "C4") (pin "1") (pinfunction "1_1") (pintype "passive"))
      (node (ref "C5") (pin "1") (pinfunction "1_1") (pintype "passive"))
      (node (ref "DIO_HSA") (pin "10") (pinfunction "10_10") (pintype "bidirectional"))
      (node (ref "DIO_HSB") (pin "10") (pinfunction "10_10") (pintype "bidirectional"))
      (node (ref "R13") (pin "2") (pinfunction "W_2") (pintype "passive"))
      (node (ref "R13") (pin "3") (pinfunction "E_3") (pintype "passive"))
      (node (ref "R14") (pin "2") (pinfunction "W_2") (pintype "passive"))
      (node (ref "R14") (pin "3") (pinfunction "E_3") (pintype "passive"))
      (node (ref "R4") (pin "1") (pinfunction "1_1") (pintype "passive"))
      (node (ref "R6") (pin "1") (pinfunction "1_1") (pintype "passive"))
      (node (ref "R7") (pin "1") (pinfunction "1_1") (pintype "passive"))
      (node (ref "TETHER") (pin "12") (pinfunction "12_12") (pintype "bidirectional"))
      (node (ref "TP1") (pin "TP") (pinfunction "TP_TP") (pintype "input"))
      (node (ref "TP10") (pin "1") (pinfunction "1_1") (pintype "passive"))
      (node (ref "TP3") (pin "TP") (pinfunction "TP_TP") (pintype "input"))
      (node (ref "TP9") (pin "1") (pinfunction "1_1") (pintype "passive"))
      (node (ref "U1") (pin "1") (pinfunction "VDD_1") (pintype "power_in"))
      (node (ref "U1") (pin "10") (pinfunction "RES1_10") (pintype "passive"))
      (node (ref "U1") (pin "9") (pinfunction "VDD_9") (pintype "power_in"))
      (node (ref "U10") (pin "5") (pinfunction "VCC_5") (pintype "power_in"))
      (node (ref "U2") (pin "1") (pinfunction "VDD_1") (pintype "power_in"))
      (node (ref "U2") (pin "10") (pinfunction "RES1_10") (pintype "passive"))
      (node (ref "U2") (pin "9") (pinfunction "VDD_9") (pintype "power_in"))
      (node (ref "U3") (pin "1") (pinfunction "VDD_1") (pintype "power_in"))
      (node (ref "U3") (pin "10") (pinfunction "RES1_10") (pintype "passive"))
      (node (ref "U3") (pin "9") (pinfunction "VDD_9") (pintype "power_in"))
      (node (ref "U4") (pin "VS1") (pinfunction "VS1_VS1") (pintype "bidirectional"))
      (node (ref "U4") (pin "VS2") (pinfunction "VS2_VS2") (pintype "bidirectional"))
      (node (ref "U5") (pin "VCC") (pinfunction "VCC_VCC") (pintype "power_in"))
      (node (ref "U6") (pin "VCC") (pinfunction "VCC_VCC") (pintype "power_in"))
      (node (ref "U7") (pin "5") (pinfunction "~{PD1}_5") (pintype "passive"))
      (node (ref "U7") (pin "8") (pinfunction "VCC_8") (pintype "power_in"))
      (node (ref "U8") (pin "5") (pinfunction "~{PD1}_5") (pintype "passive"))
      (node (ref "U8") (pin "8") (pinfunction "VCC_8") (pintype "power_in"))
      (node (ref "U9") (pin "5") (pinfunction "~{PD1}_5") (pintype "passive"))
      (node (ref "U9") (pin "8") (pinfunction "VCC_8") (pintype "power_in"))
    )
    (net (code "79") (name "unconnected-(MECH_E0B-Pad1)") (class "Default")
      (node (ref "MECH_E0B") (pin "1") (pinfunction "1_1") (pintype "bidirectional"))
    )
    (net (code "80") (name "unconnected-(MECH_E0B-Pad2)") (class "Default")
      (node (ref "MECH_E0B") (pin "2") (pinfunction "2_2") (pintype "bidirectional"))
    )
    (net (code "81") (name "unconnected-(MECH_E0B-Pad3)") (class "Default")
      (node (ref "MECH_E0B") (pin "3") (pinfunction "3_3") (pintype "bidirectional"))
    )
    (net (code "82") (name "unconnected-(MECH_E0B-Pad4)") (class "Default")
      (node (ref "MECH_E0B") (pin "4") (pinfunction "4_4") (pintype "bidirectional"))
    )
    (net (code "83") (name "unconnected-(MECH_E0B-Pad5)") (class "Default")
      (node (ref "MECH_E0B") (pin "5") (pinfunction "5_5") (pintype "bidirectional"))
    )
    (net (code "84") (name "unconnected-(MECH_E0B-Pad6)") (class "Default")
      (node (ref "MECH_E0B") (pin "6") (pinfunction "6_6") (pintype "bidirectional"))
    )
    (net (code "85") (name "unconnected-(MECH_E0B-Pad7)") (class "Default")
      (node (ref "MECH_E0B") (pin "7") (pinfunction "7_7") (pintype "bidirectional"))
    )
    (net (code "86") (name "unconnected-(MECH_E0B-Pad8)") (class "Default")
      (node (ref "MECH_E0B") (pin "8") (pinfunction "8_8") (pintype "bidirectional"))
    )
    (net (code "87") (name "unconnected-(MECH_E0B-Pad9)") (class "Default")
      (node (ref "MECH_E0B") (pin "9") (pinfunction "9_9") (pintype "bidirectional"))
    )
    (net (code "88") (name "unconnected-(MECH_E0B-Pad10)") (class "Default")
      (node (ref "MECH_E0B") (pin "10") (pinfunction "10_10") (pintype "bidirectional"))
    )
    (net (code "89") (name "unconnected-(MECH_E0B-Pad11)") (class "Default")
      (node (ref "MECH_E0B") (pin "11") (pinfunction "11_11") (pintype "bidirectional"))
    )
    (net (code "90") (name "unconnected-(MECH_E0B-Pad12)") (class "Default")
      (node (ref "MECH_E0B") (pin "12") (pinfunction "12_12") (pintype "bidirectional"))
    )
    (net (code "91") (name "unconnected-(MECH_E0B-Pad13)") (class "Default")
      (node (ref "MECH_E0B") (pin "13") (pinfunction "13_13") (pintype "bidirectional"))
    )
    (net (code "92") (name "unconnected-(MECH_E0B-Pad14)") (class "Default")
      (node (ref "MECH_E0B") (pin "14") (pinfunction "14_14") (pintype "bidirectional"))
    )
    (net (code "93") (name "unconnected-(MECH_E0B-Pad15)") (class "Default")
      (node (ref "MECH_E0B") (pin "15") (pinfunction "15_15") (pintype "bidirectional"))
    )
    (net (code "94") (name "unconnected-(MECH_E0B-Pad16)") (class "Default")
      (node (ref "MECH_E0B") (pin "16") (pinfunction "16_16") (pintype "bidirectional"))
    )
    (net (code "95") (name "unconnected-(MECH_E0B-Pad17)") (class "Default")
      (node (ref "MECH_E0B") (pin "17") (pinfunction "17_17") (pintype "bidirectional"))
    )
    (net (code "96") (name "unconnected-(MECH_E0B-Pad18)") (class "Default")
      (node (ref "MECH_E0B") (pin "18") (pinfunction "18_18") (pintype "bidirectional"))
    )
    (net (code "97") (name "unconnected-(MECH_E0B-Pad19)") (class "Default")
      (node (ref "MECH_E0B") (pin "19") (pinfunction "19_19") (pintype "bidirectional"))
    )
    (net (code "98") (name "unconnected-(MECH_E0B-Pad20)") (class "Default")
      (node (ref "MECH_E0B") (pin "20") (pinfunction "20_20") (pintype "bidirectional"))
    )
    (net (code "99") (name "unconnected-(MECH_E0B-Pad21)") (class "Default")
      (node (ref "MECH_E0B") (pin "21") (pinfunction "21_21") (pintype "bidirectional"))
    )
    (net (code "100") (name "unconnected-(MECH_E0B-Pad22)") (class "Default")
      (node (ref "MECH_E0B") (pin "22") (pinfunction "22_22") (pintype "bidirectional"))
    )
    (net (code "101") (name "unconnected-(MECH_E0B-Pad23)") (class "Default")
      (node (ref "MECH_E0B") (pin "23") (pinfunction "23_23") (pintype "bidirectional"))
    )
    (net (code "102") (name "unconnected-(MECH_E0B-Pad24)") (class "Default")
      (node (ref "MECH_E0B") (pin "24") (pinfunction "24_24") (pintype "bidirectional"))
    )
    (net (code "103") (name "unconnected-(MECH_E0B-Pad25)") (class "Default")
      (node (ref "MECH_E0B") (pin "25") (pinfunction "25_25") (pintype "bidirectional"))
    )
    (net (code "104") (name "unconnected-(MECH_E0B-Pad26)") (class "Default")
      (node (ref "MECH_E0B") (pin "26") (pinfunction "26_26") (pintype "bidirectional"))
    )
    (net (code "105") (name "unconnected-(MECH_E0B-Pad27)") (class "Default")
      (node (ref "MECH_E0B") (pin "27") (pinfunction "27_27") (pintype "bidirectional"))
    )
    (net (code "106") (name "unconnected-(MECH_E0B-Pad28)") (class "Default")
      (node (ref "MECH_E0B") (pin "28") (pinfunction "28_28") (pintype "bidirectional"))
    )
    (net (code "107") (name "unconnected-(MECH_E0B-Pad29)") (class "Default")
      (node (ref "MECH_E0B") (pin "29") (pinfunction "29_29") (pintype "bidirectional"))
    )
    (net (code "108") (name "unconnected-(MECH_E0B-Pad30)") (class "Default")
      (node (ref "MECH_E0B") (pin "30") (pinfunction "30_30") (pintype "bidirectional"))
    )
    (net (code "109") (name "unconnected-(MECH_E0B-Pad31)") (class "Default")
      (node (ref "MECH_E0B") (pin "31") (pinfunction "31_31") (pintype "bidirectional"))
    )
    (net (code "110") (name "unconnected-(MECH_E0B-Pad32)") (class "Default")
      (node (ref "MECH_E0B") (pin "32") (pinfunction "32_32") (pintype "bidirectional"))
    )
    (net (code "111") (name "unconnected-(MECH_E0B-Pad33)") (class "Default")
      (node (ref "MECH_E0B") (pin "33") (pinfunction "33_33") (pintype "bidirectional"))
    )
    (net (code "112") (name "unconnected-(MECH_E0B-Pad34)") (class "Default")
      (node (ref "MECH_E0B") (pin "34") (pinfunction "34_34") (pintype "bidirectional"))
    )
    (net (code "113") (name "unconnected-(MECH_E0B-Pad35)") (class "Default")
      (node (ref "MECH_E0B") (pin "35") (pinfunction "35_35") (pintype "bidirectional"))
    )
    (net (code "114") (name "unconnected-(MECH_E0B-Pad36)") (class "Default")
      (node (ref "MECH_E0B") (pin "36") (pinfunction "36_36") (pintype "bidirectional"))
    )
    (net (code "115") (name "unconnected-(MECH_E0B-Pad37)") (class "Default")
      (node (ref "MECH_E0B") (pin "37") (pinfunction "37_37") (pintype "bidirectional"))
    )
    (net (code "116") (name "unconnected-(MECH_E0B-Pad38)") (class "Default")
      (node (ref "MECH_E0B") (pin "38") (pinfunction "38_38") (pintype "bidirectional"))
    )
    (net (code "117") (name "unconnected-(MECH_E0B-Pad39)") (class "Default")
      (node (ref "MECH_E0B") (pin "39") (pinfunction "39_39") (pintype "bidirectional"))
    )
    (net (code "118") (name "unconnected-(MECH_E0B-Pad40)") (class "Default")
      (node (ref "MECH_E0B") (pin "40") (pinfunction "40_40") (pintype "bidirectional"))
    )
    (net (code "119") (name "unconnected-(MECH_E0B-Pad41)") (class "Default")
      (node (ref "MECH_E0B") (pin "41") (pinfunction "41_41") (pintype "bidirectional"))
    )
    (net (code "120") (name "unconnected-(MECH_E0B-Pad42)") (class "Default")
      (node (ref "MECH_E0B") (pin "42") (pinfunction "42_42") (pintype "bidirectional"))
    )
    (net (code "121") (name "unconnected-(MECH_E0B-Pad43)") (class "Default")
      (node (ref "MECH_E0B") (pin "43") (pinfunction "43_43") (pintype "bidirectional"))
    )
    (net (code "122") (name "unconnected-(MECH_E0B-Pad44)") (class "Default")
      (node (ref "MECH_E0B") (pin "44") (pinfunction "44_44") (pintype "bidirectional"))
    )
    (net (code "123") (name "unconnected-(MECH_E0B-Pad45)") (class "Default")
      (node (ref "MECH_E0B") (pin "45") (pinfunction "45_45") (pintype "bidirectional"))
    )
    (net (code "124") (name "unconnected-(MECH_E0B-Pad46)") (class "Default")
      (node (ref "MECH_E0B") (pin "46") (pinfunction "46_46") (pintype "bidirectional"))
    )
    (net (code "125") (name "unconnected-(MECH_E0B-Pad47)") (class "Default")
      (node (ref "MECH_E0B") (pin "47") (pinfunction "47_47") (pintype "bidirectional"))
    )
    (net (code "126") (name "unconnected-(MECH_E0B-Pad48)") (class "Default")
      (node (ref "MECH_E0B") (pin "48") (pinfunction "48_48") (pintype "bidirectional"))
    )
    (net (code "127") (name "unconnected-(MECH_E0B-Pad49)") (class "Default")
      (node (ref "MECH_E0B") (pin "49") (pinfunction "49_49") (pintype "bidirectional"))
    )
    (net (code "128") (name "unconnected-(MECH_E0B-Pad50)") (class "Default")
      (node (ref "MECH_E0B") (pin "50") (pinfunction "50_50") (pintype "bidirectional"))
    )
    (net (code "129") (name "unconnected-(MECH_E0B-Pad51)") (class "Default")
      (node (ref "MECH_E0B") (pin "51") (pinfunction "51_51") (pintype "bidirectional"))
    )
    (net (code "130") (name "unconnected-(MECH_E0B-Pad52)") (class "Default")
      (node (ref "MECH_E0B") (pin "52") (pinfunction "52_52") (pintype "bidirectional"))
    )
    (net (code "131") (name "unconnected-(MECH_E0B-Pad53)") (class "Default")
      (node (ref "MECH_E0B") (pin "53") (pinfunction "53_53") (pintype "bidirectional"))
    )
    (net (code "132") (name "unconnected-(MECH_E0B-Pad54)") (class "Default")
      (node (ref "MECH_E0B") (pin "54") (pinfunction "54_54") (pintype "bidirectional"))
    )
    (net (code "133") (name "unconnected-(MECH_E0B-Pad55)") (class "Default")
      (node (ref "MECH_E0B") (pin "55") (pinfunction "55_55") (pintype "bidirectional"))
    )
    (net (code "134") (name "unconnected-(MECH_E0B-Pad56)") (class "Default")
      (node (ref "MECH_E0B") (pin "56") (pinfunction "56_56") (pintype "bidirectional"))
    )
    (net (code "135") (name "unconnected-(MECH_E0B-Pad57)") (class "Default")
      (node (ref "MECH_E0B") (pin "57") (pinfunction "57_57") (pintype "bidirectional"))
    )
    (net (code "136") (name "unconnected-(MECH_E0B-Pad58)") (class "Default")
      (node (ref "MECH_E0B") (pin "58") (pinfunction "58_58") (pintype "bidirectional"))
    )
    (net (code "137") (name "unconnected-(MECH_E0B-Pad59)") (class "Default")
      (node (ref "MECH_E0B") (pin "59") (pinfunction "59_59") (pintype "bidirectional"))
    )
    (net (code "138") (name "unconnected-(MECH_E0B-Pad60)") (class "Default")
      (node (ref "MECH_E0B") (pin "60") (pinfunction "60_60") (pintype "bidirectional"))
    )
    (net (code "139") (name "unconnected-(MECH_E0B-Pad61)") (class "Default")
      (node (ref "MECH_E0B") (pin "61") (pinfunction "61_61") (pintype "bidirectional"))
    )
    (net (code "140") (name "unconnected-(MECH_E0B-Pad62)") (class "Default")
      (node (ref "MECH_E0B") (pin "62") (pinfunction "62_62") (pintype "bidirectional"))
    )
    (net (code "141") (name "unconnected-(MECH_E0B-Pad63)") (class "Default")
      (node (ref "MECH_E0B") (pin "63") (pinfunction "63_63") (pintype "bidirectional"))
    )
    (net (code "142") (name "unconnected-(MECH_E0B-Pad64)") (class "Default")
      (node (ref "MECH_E0B") (pin "64") (pinfunction "64_64") (pintype "bidirectional"))
    )
    (net (code "143") (name "unconnected-(MECH_E0B-Pad65)") (class "Default")
      (node (ref "MECH_E0B") (pin "65") (pinfunction "65_65") (pintype "bidirectional"))
    )
    (net (code "144") (name "unconnected-(MECH_E0B-Pad66)") (class "Default")
      (node (ref "MECH_E0B") (pin "66") (pinfunction "66_66") (pintype "bidirectional"))
    )
    (net (code "145") (name "unconnected-(MECH_E0B-Pad67)") (class "Default")
      (node (ref "MECH_E0B") (pin "67") (pinfunction "67_67") (pintype "bidirectional"))
    )
    (net (code "146") (name "unconnected-(MECH_E0B-Pad68)") (class "Default")
      (node (ref "MECH_E0B") (pin "68") (pinfunction "68_68") (pintype "bidirectional"))
    )
    (net (code "147") (name "unconnected-(MECH_E0B-Pad69)") (class "Default")
      (node (ref "MECH_E0B") (pin "69") (pinfunction "69_69") (pintype "bidirectional"))
    )
    (net (code "148") (name "unconnected-(MECH_E0B-Pad70)") (class "Default")
      (node (ref "MECH_E0B") (pin "70") (pinfunction "70_70") (pintype "bidirectional"))
    )
    (net (code "149") (name "unconnected-(MECH_W0B-Pad1)") (class "Default")
      (node (ref "MECH_W0B") (pin "1") (pinfunction "1_1") (pintype "bidirectional"))
    )
    (net (code "150") (name "unconnected-(MECH_W0B-Pad2)") (class "Default")
      (node (ref "MECH_W0B") (pin "2") (pinfunction "2_2") (pintype "bidirectional"))
    )
    (net (code "151") (name "unconnected-(MECH_W0B-Pad3)") (class "Default")
      (node (ref "MECH_W0B") (pin "3") (pinfunction "3_3") (pintype "bidirectional"))
    )
    (net (code "152") (name "unconnected-(MECH_W0B-Pad4)") (class "Default")
      (node (ref "MECH_W0B") (pin "4") (pinfunction "4_4") (pintype "bidirectional"))
    )
    (net (code "153") (name "unconnected-(MECH_W0B-Pad5)") (class "Default")
      (node (ref "MECH_W0B") (pin "5") (pinfunction "5_5") (pintype "bidirectional"))
    )
    (net (code "154") (name "unconnected-(MECH_W0B-Pad6)") (class "Default")
      (node (ref "MECH_W0B") (pin "6") (pinfunction "6_6") (pintype "bidirectional"))
    )
    (net (code "155") (name "unconnected-(MECH_W0B-Pad7)") (class "Default")
      (node (ref "MECH_W0B") (pin "7") (pinfunction "7_7") (pintype "bidirectional"))
    )
    (net (code "156") (name "unconnected-(MECH_W0B-Pad8)") (class "Default")
      (node (ref "MECH_W0B") (pin "8") (pinfunction "8_8") (pintype "bidirectional"))
    )
    (net (code "157") (name "unconnected-(MECH_W0B-Pad9)") (class "Default")
      (node (ref "MECH_W0B") (pin "9") (pinfunction "9_9") (pintype "bidirectional"))
    )
    (net (code "158") (name "unconnected-(MECH_W0B-Pad10)") (class "Default")
      (node (ref "MECH_W0B") (pin "10") (pinfunction "10_10") (pintype "bidirectional"))
    )
    (net (code "159") (name "unconnected-(MECH_W0B-Pad11)") (class "Default")
      (node (ref "MECH_W0B") (pin "11") (pinfunction "11_11") (pintype "bidirectional"))
    )
    (net (code "160") (name "unconnected-(MECH_W0B-Pad12)") (class "Default")
      (node (ref "MECH_W0B") (pin "12") (pinfunction "12_12") (pintype "bidirectional"))
    )
    (net (code "161") (name "unconnected-(MECH_W0B-Pad13)") (class "Default")
      (node (ref "MECH_W0B") (pin "13") (pinfunction "13_13") (pintype "bidirectional"))
    )
    (net (code "162") (name "unconnected-(MECH_W0B-Pad14)") (class "Default")
      (node (ref "MECH_W0B") (pin "14") (pinfunction "14_14") (pintype "bidirectional"))
    )
    (net (code "163") (name "unconnected-(MECH_W0B-Pad15)") (class "Default")
      (node (ref "MECH_W0B") (pin "15") (pinfunction "15_15") (pintype "bidirectional"))
    )
    (net (code "164") (name "unconnected-(MECH_W0B-Pad16)") (class "Default")
      (node (ref "MECH_W0B") (pin "16") (pinfunction "16_16") (pintype "bidirectional"))
    )
    (net (code "165") (name "unconnected-(MECH_W0B-Pad17)") (class "Default")
      (node (ref "MECH_W0B") (pin "17") (pinfunction "17_17") (pintype "bidirectional"))
    )
    (net (code "166") (name "unconnected-(MECH_W0B-Pad18)") (class "Default")
      (node (ref "MECH_W0B") (pin "18") (pinfunction "18_18") (pintype "bidirectional"))
    )
    (net (code "167") (name "unconnected-(MECH_W0B-Pad19)") (class "Default")
      (node (ref "MECH_W0B") (pin "19") (pinfunction "19_19") (pintype "bidirectional"))
    )
    (net (code "168") (name "unconnected-(MECH_W0B-Pad20)") (class "Default")
      (node (ref "MECH_W0B") (pin "20") (pinfunction "20_20") (pintype "bidirectional"))
    )
    (net (code "169") (name "unconnected-(MECH_W0B-Pad21)") (class "Default")
      (node (ref "MECH_W0B") (pin "21") (pinfunction "21_21") (pintype "bidirectional"))
    )
    (net (code "170") (name "unconnected-(MECH_W0B-Pad22)") (class "Default")
      (node (ref "MECH_W0B") (pin "22") (pinfunction "22_22") (pintype "bidirectional"))
    )
    (net (code "171") (name "unconnected-(MECH_W0B-Pad23)") (class "Default")
      (node (ref "MECH_W0B") (pin "23") (pinfunction "23_23") (pintype "bidirectional"))
    )
    (net (code "172") (name "unconnected-(MECH_W0B-Pad24)") (class "Default")
      (node (ref "MECH_W0B") (pin "24") (pinfunction "24_24") (pintype "bidirectional"))
    )
    (net (code "173") (name "unconnected-(MECH_W0B-Pad25)") (class "Default")
      (node (ref "MECH_W0B") (pin "25") (pinfunction "25_25") (pintype "bidirectional"))
    )
    (net (code "174") (name "unconnected-(MECH_W0B-Pad26)") (class "Default")
      (node (ref "MECH_W0B") (pin "26") (pinfunction "26_26") (pintype "bidirectional"))
    )
    (net (code "175") (name "unconnected-(MECH_W0B-Pad27)") (class "Default")
      (node (ref "MECH_W0B") (pin "27") (pinfunction "27_27") (pintype "bidirectional"))
    )
    (net (code "176") (name "unconnected-(MECH_W0B-Pad28)") (class "Default")
      (node (ref "MECH_W0B") (pin "28") (pinfunction "28_28") (pintype "bidirectional"))
    )
    (net (code "177") (name "unconnected-(MECH_W0B-Pad29)") (class "Default")
      (node (ref "MECH_W0B") (pin "29") (pinfunction "29_29") (pintype "bidirectional"))
    )
    (net (code "178") (name "unconnected-(MECH_W0B-Pad30)") (class "Default")
      (node (ref "MECH_W0B") (pin "30") (pinfunction "30_30") (pintype "bidirectional"))
    )
    (net (code "179") (name "unconnected-(MECH_W0B-Pad31)") (class "Default")
      (node (ref "MECH_W0B") (pin "31") (pinfunction "31_31") (pintype "bidirectional"))
    )
    (net (code "180") (name "unconnected-(MECH_W0B-Pad32)") (class "Default")
      (node (ref "MECH_W0B") (pin "32") (pinfunction "32_32") (pintype "bidirectional"))
    )
    (net (code "181") (name "unconnected-(MECH_W0B-Pad33)") (class "Default")
      (node (ref "MECH_W0B") (pin "33") (pinfunction "33_33") (pintype "bidirectional"))
    )
    (net (code "182") (name "unconnected-(MECH_W0B-Pad34)") (class "Default")
      (node (ref "MECH_W0B") (pin "34") (pinfunction "34_34") (pintype "bidirectional"))
    )
    (net (code "183") (name "unconnected-(MECH_W0B-Pad35)") (class "Default")
      (node (ref "MECH_W0B") (pin "35") (pinfunction "35_35") (pintype "bidirectional"))
    )
    (net (code "184") (name "unconnected-(MECH_W0B-Pad36)") (class "Default")
      (node (ref "MECH_W0B") (pin "36") (pinfunction "36_36") (pintype "bidirectional"))
    )
    (net (code "185") (name "unconnected-(MECH_W0B-Pad37)") (class "Default")
      (node (ref "MECH_W0B") (pin "37") (pinfunction "37_37") (pintype "bidirectional"))
    )
    (net (code "186") (name "unconnected-(MECH_W0B-Pad38)") (class "Default")
      (node (ref "MECH_W0B") (pin "38") (pinfunction "38_38") (pintype "bidirectional"))
    )
    (net (code "187") (name "unconnected-(MECH_W0B-Pad39)") (class "Default")
      (node (ref "MECH_W0B") (pin "39") (pinfunction "39_39") (pintype "bidirectional"))
    )
    (net (code "188") (name "unconnected-(MECH_W0B-Pad40)") (class "Default")
      (node (ref "MECH_W0B") (pin "40") (pinfunction "40_40") (pintype "bidirectional"))
    )
    (net (code "189") (name "unconnected-(MECH_W0B-Pad41)") (class "Default")
      (node (ref "MECH_W0B") (pin "41") (pinfunction "41_41") (pintype "bidirectional"))
    )
    (net (code "190") (name "unconnected-(MECH_W0B-Pad42)") (class "Default")
      (node (ref "MECH_W0B") (pin "42") (pinfunction "42_42") (pintype "bidirectional"))
    )
    (net (code "191") (name "unconnected-(MECH_W0B-Pad43)") (class "Default")
      (node (ref "MECH_W0B") (pin "43") (pinfunction "43_43") (pintype "bidirectional"))
    )
    (net (code "192") (name "unconnected-(MECH_W0B-Pad44)") (class "Default")
      (node (ref "MECH_W0B") (pin "44") (pinfunction "44_44") (pintype "bidirectional"))
    )
    (net (code "193") (name "unconnected-(MECH_W0B-Pad45)") (class "Default")
      (node (ref "MECH_W0B") (pin "45") (pinfunction "45_45") (pintype "bidirectional"))
    )
    (net (code "194") (name "unconnected-(MECH_W0B-Pad46)") (class "Default")
      (node (ref "MECH_W0B") (pin "46") (pinfunction "46_46") (pintype "bidirectional"))
    )
    (net (code "195") (name "unconnected-(MECH_W0B-Pad47)") (class "Default")
      (node (ref "MECH_W0B") (pin "47") (pinfunction "47_47") (pintype "bidirectional"))
    )
    (net (code "196") (name "unconnected-(MECH_W0B-Pad48)") (class "Default")
      (node (ref "MECH_W0B") (pin "48") (pinfunction "48_48") (pintype "bidirectional"))
    )
    (net (code "197") (name "unconnected-(MECH_W0B-Pad49)") (class "Default")
      (node (ref "MECH_W0B") (pin "49") (pinfunction "49_49") (pintype "bidirectional"))
    )
    (net (code "198") (name "unconnected-(MECH_W0B-Pad50)") (class "Default")
      (node (ref "MECH_W0B") (pin "50") (pinfunction "50_50") (pintype "bidirectional"))
    )
    (net (code "199") (name "unconnected-(MECH_W0B-Pad51)") (class "Default")
      (node (ref "MECH_W0B") (pin "51") (pinfunction "51_51") (pintype "bidirectional"))
    )
    (net (code "200") (name "unconnected-(MECH_W0B-Pad52)") (class "Default")
      (node (ref "MECH_W0B") (pin "52") (pinfunction "52_52") (pintype "bidirectional"))
    )
    (net (code "201") (name "unconnected-(MECH_W0B-Pad53)") (class "Default")
      (node (ref "MECH_W0B") (pin "53") (pinfunction "53_53") (pintype "bidirectional"))
    )
    (net (code "202") (name "unconnected-(MECH_W0B-Pad54)") (class "Default")
      (node (ref "MECH_W0B") (pin "54") (pinfunction "54_54") (pintype "bidirectional"))
    )
    (net (code "203") (name "unconnected-(MECH_W0B-Pad55)") (class "Default")
      (node (ref "MECH_W0B") (pin "55") (pinfunction "55_55") (pintype "bidirectional"))
    )
    (net (code "204") (name "unconnected-(MECH_W0B-Pad56)") (class "Default")
      (node (ref "MECH_W0B") (pin "56") (pinfunction "56_56") (pintype "bidirectional"))
    )
    (net (code "205") (name "unconnected-(MECH_W0B-Pad57)") (class "Default")
      (node (ref "MECH_W0B") (pin "57") (pinfunction "57_57") (pintype "bidirectional"))
    )
    (net (code "206") (name "unconnected-(MECH_W0B-Pad58)") (class "Default")
      (node (ref "MECH_W0B") (pin "58") (pinfunction "58_58") (pintype "bidirectional"))
    )
    (net (code "207") (name "unconnected-(MECH_W0B-Pad59)") (class "Default")
      (node (ref "MECH_W0B") (pin "59") (pinfunction "59_59") (pintype "bidirectional"))
    )
    (net (code "208") (name "unconnected-(MECH_W0B-Pad60)") (class "Default")
      (node (ref "MECH_W0B") (pin "60") (pinfunction "60_60") (pintype "bidirectional"))
    )
    (net (code "209") (name "unconnected-(MECH_W0B-Pad61)") (class "Default")
      (node (ref "MECH_W0B") (pin "61") (pinfunction "61_61") (pintype "bidirectional"))
    )
    (net (code "210") (name "unconnected-(MECH_W0B-Pad62)") (class "Default")
      (node (ref "MECH_W0B") (pin "62") (pinfunction "62_62") (pintype "bidirectional"))
    )
    (net (code "211") (name "unconnected-(MECH_W0B-Pad63)") (class "Default")
      (node (ref "MECH_W0B") (pin "63") (pinfunction "63_63") (pintype "bidirectional"))
    )
    (net (code "212") (name "unconnected-(MECH_W0B-Pad64)") (class "Default")
      (node (ref "MECH_W0B") (pin "64") (pinfunction "64_64") (pintype "bidirectional"))
    )
    (net (code "213") (name "unconnected-(MECH_W0B-Pad65)") (class "Default")
      (node (ref "MECH_W0B") (pin "65") (pinfunction "65_65") (pintype "bidirectional"))
    )
    (net (code "214") (name "unconnected-(MECH_W0B-Pad66)") (class "Default")
      (node (ref "MECH_W0B") (pin "66") (pinfunction "66_66") (pintype "bidirectional"))
    )
    (net (code "215") (name "unconnected-(MECH_W0B-Pad67)") (class "Default")
      (node (ref "MECH_W0B") (pin "67") (pinfunction "67_67") (pintype "bidirectional"))
    )
    (net (code "216") (name "unconnected-(MECH_W0B-Pad68)") (class "Default")
      (node (ref "MECH_W0B") (pin "68") (pinfunction "68_68") (pintype "bidirectional"))
    )
    (net (code "217") (name "unconnected-(MECH_W0B-Pad69)") (class "Default")
      (node (ref "MECH_W0B") (pin "69") (pinfunction "69_69") (pintype "bidirectional"))
    )
    (net (code "218") (name "unconnected-(MECH_W0B-Pad70)") (class "Default")
      (node (ref "MECH_W0B") (pin "70") (pinfunction "70_70") (pintype "bidirectional"))
    )
    (net (code "219") (name "unconnected-(U1-RES-Pad5)") (class "Default")
      (node (ref "U1") (pin "5") (pinfunction "RES_5") (pintype "passive"))
    )
    (net (code "220") (name "unconnected-(U2-RES-Pad5)") (class "Default")
      (node (ref "U2") (pin "5") (pinfunction "RES_5") (pintype "passive"))
    )
    (net (code "221") (name "unconnected-(U3-RES-Pad5)") (class "Default")
      (node (ref "U3") (pin "5") (pinfunction "RES_5") (pintype "passive"))
    )
    (net (code "222") (name "unconnected-(U4-PadNC1)") (class "Default")
      (node (ref "U4") (pin "NC1") (pinfunction "NC1_NC1") (pintype "bidirectional"))
    )
    (net (code "223") (name "unconnected-(U4-PadNC2)") (class "Default")
      (node (ref "U4") (pin "NC2") (pinfunction "NC2_NC2") (pintype "bidirectional"))
    )
    (net (code "224") (name "unconnected-(U4-PadNC3)") (class "Default")
      (node (ref "U4") (pin "NC3") (pinfunction "NC3_NC3") (pintype "bidirectional"))
    )
    (net (code "225") (name "unconnected-(U4-PadNC4)") (class "Default")
      (node (ref "U4") (pin "NC4") (pinfunction "NC4_NC4") (pintype "bidirectional"))
    )
    (net (code "226") (name "unconnected-(U4-PadNC5)") (class "Default")
      (node (ref "U4") (pin "NC5") (pinfunction "NC5_NC5") (pintype "bidirectional"))
    )
    (net (code "227") (name "unconnected-(U4-PadNC6)") (class "Default")
      (node (ref "U4") (pin "NC6") (pinfunction "NC6_NC6") (pintype "bidirectional"))
    )
  )
)
